# RaspberryPI4.net
KiCad netlist of a schematic drawn in Altium Designer
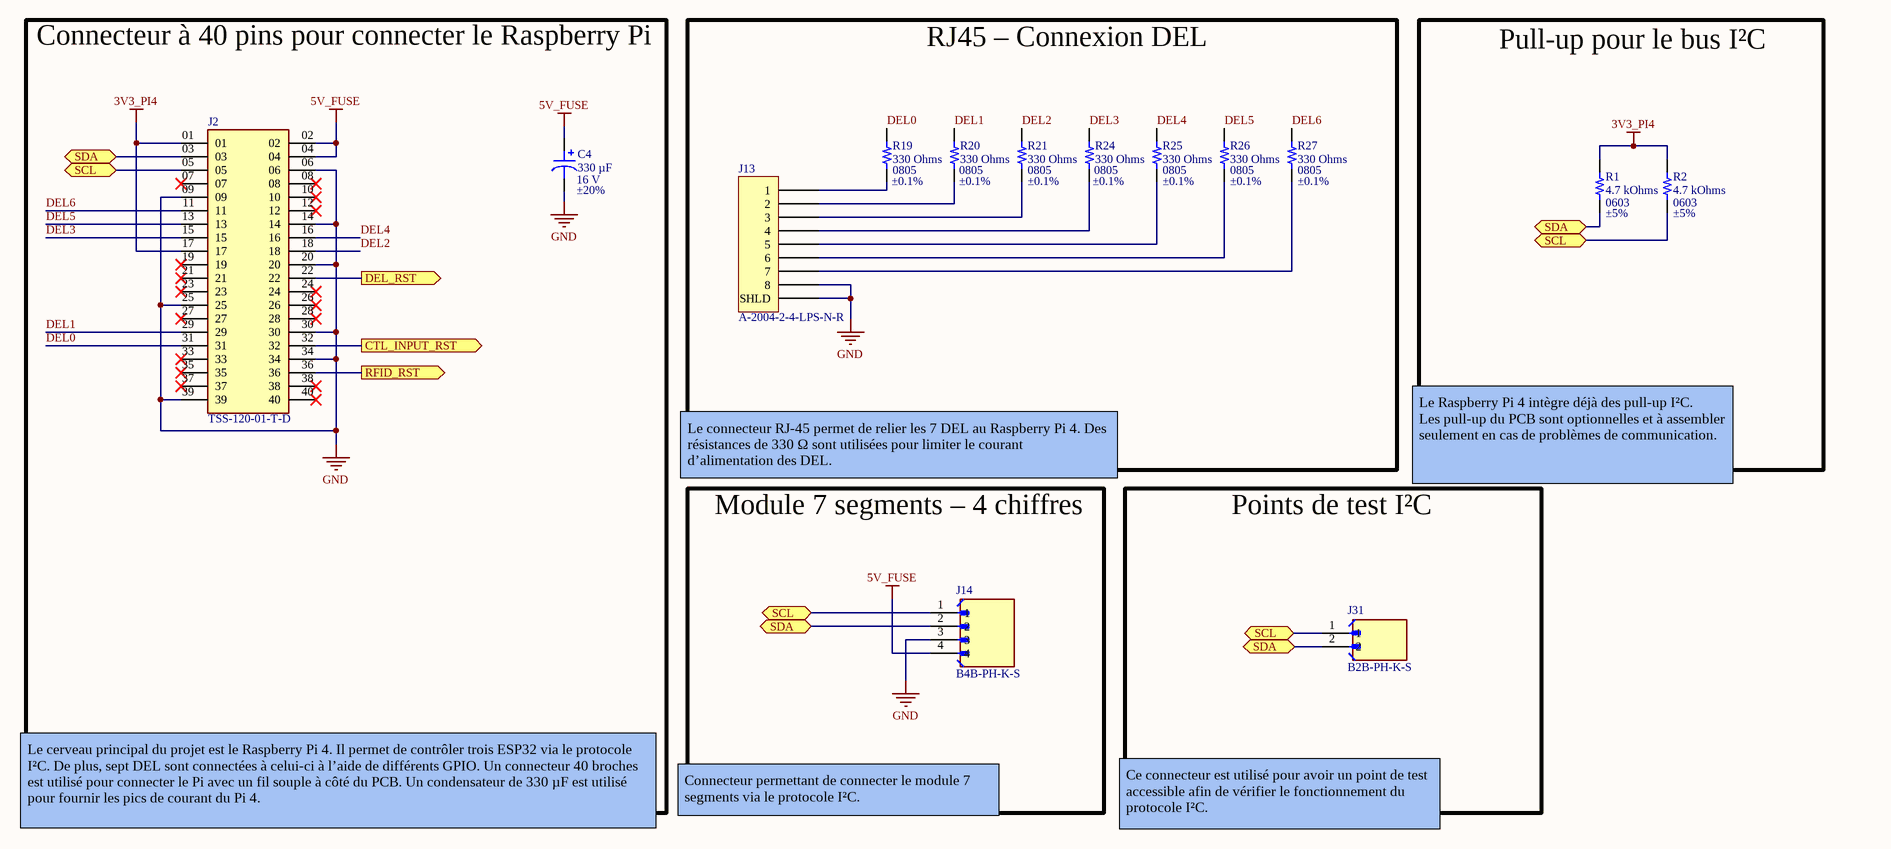
[diagram p0: RaspberryPI4.SchDoc]

(export (version "E")
  (design (tool "Eeschema 10.0.6"))
  (components
    (comp (ref "C4")
      (value "330 µF")
      (footprint "CAP ALSMD 8.3MM H10.5MM")
      (description "CAP ALUM 330UF 20% 16V SMD")
      (fields
        (field (name "PART NUMBER") "865060353008")
        (field (name "MANUFACTURER") "Würth Elektronik")
        (field (name "TOLERANCE") "±20%")
        (field (name "VOLTAGE - RATED") "16 V")
      )
      (libsource (lib "Celestial Altium Library - altium_library") (part "Polarised Capacitor"))
    )
    (comp (ref "J2")
      (value "TSS-120-01-T-D")
      (footprint "SAMTEC_TSS-120-01-T-D")
      (description "Connector Header Through Hole 40 position 0.100 (2.54mm)")
      (fields (field (name "MF") "Samtec"))
      (libsource (lib "TSS-120-01-T-D") (part "TSS-120-01-T-D"))
    )
    (comp (ref "J13")
      (value "A-2004-2-4-LPS-N-R")
      (footprint "ASSMANN A-2004-2-4-LPS-N-R")
      (description "CONN MOD JACK 8P8C R/A SHIELDED")
      (fields (field (name "MANUFACTURER") "Assmann WSW Components"))
      (libsource (lib "Celestial Altium Library - altium_library") (part "Modular Jack with Shield"))
    )
    (comp (ref "J14")
      (value "B4B-PH-K-S")
      (footprint "JST_B4B-PH-K-S")
      (fields (field (name "MF") "{'manufacturer': u'JST Sales America Inc.'}"))
      (libsource (lib "B4B-PH-K-S") (part "B4B-PH-K-S"))
    )
    (comp (ref "J31")
      (value "B2B-PH-K-S")
      (footprint "JST_B2B-PH-K-S")
      (description "Connector Header Through Hole 2 position 0.079 (2.00mm)")
      (fields (field (name "MF") "JST Sales America Inc."))
      (libsource (lib "B2B-PH-K-S") (part "B2B-PH-K-S"))
    )
    (comp (ref "R1")
      (value "4.7 kOhms")
      (footprint "RES 0603_1608")
      (description "RES SMD 4.7K OHM 5% 1/4W 0603")
      (fields
        (field (name "PART NUMBER") "ESR03EZPJ472")
        (field (name "MANUFACTURER") "Rohm Semiconductor")
        (field (name "SUPPLIER DEVICE PACKAGE") "0603")
        (field (name "TOLERANCE") "±5%")
      )
      (libsource (lib "Celestial Altium Library - altium_library") (part "Resistor"))
    )
    (comp (ref "R2")
      (value "4.7 kOhms")
      (footprint "RES 0603_1608")
      (description "RES SMD 4.7K OHM 5% 1/4W 0603")
      (fields
        (field (name "PART NUMBER") "ESR03EZPJ472")
        (field (name "MANUFACTURER") "Rohm Semiconductor")
        (field (name "SUPPLIER DEVICE PACKAGE") "0603")
        (field (name "TOLERANCE") "±5%")
      )
      (libsource (lib "Celestial Altium Library - altium_library") (part "Resistor"))
    )
    (comp (ref "R19")
      (value "330 Ohms")
      (footprint "RES 0805_2012")
      (description "RES SMD 330 OHM 0.1% 1/4W 0805")
      (fields
        (field (name "PART NUMBER") "ERJ-PB6B3300V")
        (field (name "MANUFACTURER") "Panasonic Electronic Components")
        (field (name "SUPPLIER DEVICE PACKAGE") "0805")
        (field (name "TOLERANCE") "±0.1%")
      )
      (libsource (lib "Celestial Altium Library - altium_library") (part "Resistor"))
    )
    (comp (ref "R20")
      (value "330 Ohms")
      (footprint "RES 0805_2012")
      (description "RES SMD 330 OHM 0.1% 1/4W 0805")
      (fields
        (field (name "PART NUMBER") "ERJ-PB6B3300V")
        (field (name "MANUFACTURER") "Panasonic Electronic Components")
        (field (name "SUPPLIER DEVICE PACKAGE") "0805")
        (field (name "TOLERANCE") "±0.1%")
      )
      (libsource (lib "Celestial Altium Library - altium_library") (part "Resistor"))
    )
    (comp (ref "R21")
      (value "330 Ohms")
      (footprint "RES 0805_2012")
      (description "RES SMD 330 OHM 0.1% 1/4W 0805")
      (fields
        (field (name "PART NUMBER") "ERJ-PB6B3300V")
        (field (name "MANUFACTURER") "Panasonic Electronic Components")
        (field (name "SUPPLIER DEVICE PACKAGE") "0805")
        (field (name "TOLERANCE") "±0.1%")
      )
      (libsource (lib "Celestial Altium Library - altium_library") (part "Resistor"))
    )
    (comp (ref "R24")
      (value "330 Ohms")
      (footprint "RES 0805_2012")
      (description "RES SMD 330 OHM 0.1% 1/4W 0805")
      (fields
        (field (name "PART NUMBER") "ERJ-PB6B3300V")
        (field (name "MANUFACTURER") "Panasonic Electronic Components")
        (field (name "SUPPLIER DEVICE PACKAGE") "0805")
        (field (name "TOLERANCE") "±0.1%")
      )
      (libsource (lib "Celestial Altium Library - altium_library") (part "Resistor"))
    )
    (comp (ref "R25")
      (value "330 Ohms")
      (footprint "RES 0805_2012")
      (description "RES SMD 330 OHM 0.1% 1/4W 0805")
      (fields
        (field (name "PART NUMBER") "ERJ-PB6B3300V")
        (field (name "MANUFACTURER") "Panasonic Electronic Components")
        (field (name "SUPPLIER DEVICE PACKAGE") "0805")
        (field (name "TOLERANCE") "±0.1%")
      )
      (libsource (lib "Celestial Altium Library - altium_library") (part "Resistor"))
    )
    (comp (ref "R26")
      (value "330 Ohms")
      (footprint "RES 0805_2012")
      (description "RES SMD 330 OHM 0.1% 1/4W 0805")
      (fields
        (field (name "PART NUMBER") "ERJ-PB6B3300V")
        (field (name "MANUFACTURER") "Panasonic Electronic Components")
        (field (name "SUPPLIER DEVICE PACKAGE") "0805")
        (field (name "TOLERANCE") "±0.1%")
      )
      (libsource (lib "Celestial Altium Library - altium_library") (part "Resistor"))
    )
    (comp (ref "R27")
      (value "330 Ohms")
      (footprint "RES 0805_2012")
      (description "RES SMD 330 OHM 0.1% 1/4W 0805")
      (fields
        (field (name "PART NUMBER") "ERJ-PB6B3300V")
        (field (name "MANUFACTURER") "Panasonic Electronic Components")
        (field (name "SUPPLIER DEVICE PACKAGE") "0805")
        (field (name "TOLERANCE") "±0.1%")
      )
      (libsource (lib "Celestial Altium Library - altium_library") (part "Resistor"))
    )
  )
  (nets
    (net (code "1") (name "/CTL_INPUT_RST") (class "Default")
      (node (ref "J2") (pin "32") (pinfunction "32_32") (pintype "passive"))
    )
    (net (code "2") (name "/DEL0") (class "Default")
      (node (ref "J2") (pin "31") (pinfunction "31_31") (pintype "passive"))
      (node (ref "R19") (pin "2") (pinfunction "2_2") (pintype "passive"))
    )
    (net (code "3") (name "/DEL1") (class "Default")
      (node (ref "J2") (pin "29") (pinfunction "29_29") (pintype "passive"))
      (node (ref "R20") (pin "2") (pinfunction "2_2") (pintype "passive"))
    )
    (net (code "4") (name "/DEL2") (class "Default")
      (node (ref "J2") (pin "18") (pinfunction "18_18") (pintype "passive"))
      (node (ref "R21") (pin "2") (pinfunction "2_2") (pintype "passive"))
    )
    (net (code "5") (name "/DEL3") (class "Default")
      (node (ref "J2") (pin "15") (pinfunction "15_15") (pintype "passive"))
      (node (ref "R24") (pin "2") (pinfunction "2_2") (pintype "passive"))
    )
    (net (code "6") (name "/DEL4") (class "Default")
      (node (ref "J2") (pin "16") (pinfunction "16_16") (pintype "passive"))
      (node (ref "R25") (pin "2") (pinfunction "2_2") (pintype "passive"))
    )
    (net (code "7") (name "/DEL5") (class "Default")
      (node (ref "J2") (pin "13") (pinfunction "13_13") (pintype "passive"))
      (node (ref "R26") (pin "2") (pinfunction "2_2") (pintype "passive"))
    )
    (net (code "8") (name "/DEL6") (class "Default")
      (node (ref "J2") (pin "11") (pinfunction "11_11") (pintype "passive"))
      (node (ref "R27") (pin "2") (pinfunction "2_2") (pintype "passive"))
    )
    (net (code "9") (name "/DEL_RST") (class "Default")
      (node (ref "J2") (pin "22") (pinfunction "22_22") (pintype "passive"))
    )
    (net (code "10") (name "/RFID_RST") (class "Default")
      (node (ref "J2") (pin "36") (pinfunction "36_36") (pintype "passive"))
    )
    (net (code "11") (name "/SCL") (class "Default")
      (node (ref "J14") (pin "1") (pinfunction "1_1") (pintype "passive"))
      (node (ref "J2") (pin "05") (pinfunction "05_05") (pintype "passive"))
      (node (ref "J31") (pin "1") (pinfunction "1_1") (pintype "passive"))
      (node (ref "R2") (pin "1") (pinfunction "1_1") (pintype "passive"))
    )
    (net (code "12") (name "/SDA") (class "Default")
      (node (ref "J14") (pin "2") (pinfunction "2_2") (pintype "passive"))
      (node (ref "J2") (pin "03") (pinfunction "03_03") (pintype "passive"))
      (node (ref "J31") (pin "2") (pinfunction "2_2") (pintype "passive"))
      (node (ref "R1") (pin "1") (pinfunction "1_1") (pintype "passive"))
    )
    (net (code "13") (name "3V3_PI4") (class "Default")
      (node (ref "J2") (pin "01") (pinfunction "01_01") (pintype "passive"))
      (node (ref "J2") (pin "17") (pinfunction "17_17") (pintype "passive"))
      (node (ref "R1") (pin "2") (pinfunction "2_2") (pintype "passive"))
      (node (ref "R2") (pin "2") (pinfunction "2_2") (pintype "passive"))
    )
    (net (code "14") (name "5V_FUSE") (class "Default")
      (node (ref "C4") (pin "1") (pinfunction "1_1") (pintype "passive"))
      (node (ref "J14") (pin "4") (pinfunction "4_4") (pintype "passive"))
      (node (ref "J2") (pin "02") (pinfunction "02_02") (pintype "passive"))
      (node (ref "J2") (pin "04") (pinfunction "04_04") (pintype "passive"))
    )
    (net (code "15") (name "GND") (class "Default")
      (node (ref "C4") (pin "2") (pinfunction "2_2") (pintype "passive"))
      (node (ref "J13") (pin "8") (pinfunction "8_8") (pintype "passive"))
      (node (ref "J13") (pin "S") (pinfunction "SHLD_S") (pintype "passive"))
      (node (ref "J14") (pin "3") (pinfunction "3_3") (pintype "passive"))
      (node (ref "J2") (pin "06") (pinfunction "06_06") (pintype "passive"))
      (node (ref "J2") (pin "09") (pinfunction "09_09") (pintype "passive"))
      (node (ref "J2") (pin "14") (pinfunction "14_14") (pintype "passive"))
      (node (ref "J2") (pin "20") (pinfunction "20_20") (pintype "passive"))
      (node (ref "J2") (pin "25") (pinfunction "25_25") (pintype "passive"))
      (node (ref "J2") (pin "30") (pinfunction "30_30") (pintype "passive"))
      (node (ref "J2") (pin "34") (pinfunction "34_34") (pintype "passive"))
      (node (ref "J2") (pin "39") (pinfunction "39_39") (pintype "passive"))
    )
    (net (code "16") (name "Net-(J13-Pad1)") (class "Default")
      (node (ref "J13") (pin "1") (pinfunction "1_1") (pintype "passive"))
      (node (ref "R19") (pin "1") (pinfunction "1_1") (pintype "passive"))
    )
    (net (code "17") (name "Net-(J13-Pad2)") (class "Default")
      (node (ref "J13") (pin "2") (pinfunction "2_2") (pintype "passive"))
      (node (ref "R20") (pin "1") (pinfunction "1_1") (pintype "passive"))
    )
    (net (code "18") (name "Net-(J13-Pad3)") (class "Default")
      (node (ref "J13") (pin "3") (pinfunction "3_3") (pintype "passive"))
      (node (ref "R21") (pin "1") (pinfunction "1_1") (pintype "passive"))
    )
    (net (code "19") (name "Net-(J13-Pad4)") (class "Default")
      (node (ref "J13") (pin "4") (pinfunction "4_4") (pintype "passive"))
      (node (ref "R24") (pin "1") (pinfunction "1_1") (pintype "passive"))
    )
    (net (code "20") (name "Net-(J13-Pad5)") (class "Default")
      (node (ref "J13") (pin "5") (pinfunction "5_5") (pintype "passive"))
      (node (ref "R25") (pin "1") (pinfunction "1_1") (pintype "passive"))
    )
    (net (code "21") (name "Net-(J13-Pad6)") (class "Default")
      (node (ref "J13") (pin "6") (pinfunction "6_6") (pintype "passive"))
      (node (ref "R26") (pin "1") (pinfunction "1_1") (pintype "passive"))
    )
    (net (code "22") (name "Net-(J13-Pad7)") (class "Default")
      (node (ref "J13") (pin "7") (pinfunction "7_7") (pintype "passive"))
      (node (ref "R27") (pin "1") (pinfunction "1_1") (pintype "passive"))
    )
    (net (code "23") (name "unconnected-(J2-Pad07)") (class "Default")
      (node (ref "J2") (pin "07") (pinfunction "07_07") (pintype "passive+no_connect"))
    )
    (net (code "24") (name "unconnected-(J2-Pad08)") (class "Default")
      (node (ref "J2") (pin "08") (pinfunction "08_08") (pintype "passive+no_connect"))
    )
    (net (code "25") (name "unconnected-(J2-Pad10)") (class "Default")
      (node (ref "J2") (pin "10") (pinfunction "10_10") (pintype "passive+no_connect"))
    )
    (net (code "26") (name "unconnected-(J2-Pad12)") (class "Default")
      (node (ref "J2") (pin "12") (pinfunction "12_12") (pintype "passive+no_connect"))
    )
    (net (code "27") (name "unconnected-(J2-Pad19)") (class "Default")
      (node (ref "J2") (pin "19") (pinfunction "19_19") (pintype "passive+no_connect"))
    )
    (net (code "28") (name "unconnected-(J2-Pad21)") (class "Default")
      (node (ref "J2") (pin "21") (pinfunction "21_21") (pintype "passive+no_connect"))
    )
    (net (code "29") (name "unconnected-(J2-Pad23)") (class "Default")
      (node (ref "J2") (pin "23") (pinfunction "23_23") (pintype "passive+no_connect"))
    )
    (net (code "30") (name "unconnected-(J2-Pad24)") (class "Default")
      (node (ref "J2") (pin "24") (pinfunction "24_24") (pintype "passive+no_connect"))
    )
    (net (code "31") (name "unconnected-(J2-Pad26)") (class "Default")
      (node (ref "J2") (pin "26") (pinfunction "26_26") (pintype "passive+no_connect"))
    )
    (net (code "32") (name "unconnected-(J2-Pad27)") (class "Default")
      (node (ref "J2") (pin "27") (pinfunction "27_27") (pintype "passive+no_connect"))
    )
    (net (code "33") (name "unconnected-(J2-Pad28)") (class "Default")
      (node (ref "J2") (pin "28") (pinfunction "28_28") (pintype "passive+no_connect"))
    )
    (net (code "34") (name "unconnected-(J2-Pad33)") (class "Default")
      (node (ref "J2") (pin "33") (pinfunction "33_33") (pintype "passive+no_connect"))
    )
    (net (code "35") (name "unconnected-(J2-Pad35)") (class "Default")
      (node (ref "J2") (pin "35") (pinfunction "35_35") (pintype "passive+no_connect"))
    )
    (net (code "36") (name "unconnected-(J2-Pad37)") (class "Default")
      (node (ref "J2") (pin "37") (pinfunction "37_37") (pintype "passive+no_connect"))
    )
    (net (code "37") (name "unconnected-(J2-Pad38)") (class "Default")
      (node (ref "J2") (pin "38") (pinfunction "38_38") (pintype "passive+no_connect"))
    )
    (net (code "38") (name "unconnected-(J2-Pad40)") (class "Default")
      (node (ref "J2") (pin "40") (pinfunction "40_40") (pintype "passive+no_connect"))
    )
  )
)
